# 08_Programming_Reset.net
KiCad netlist of a schematic drawn in Altium Designer
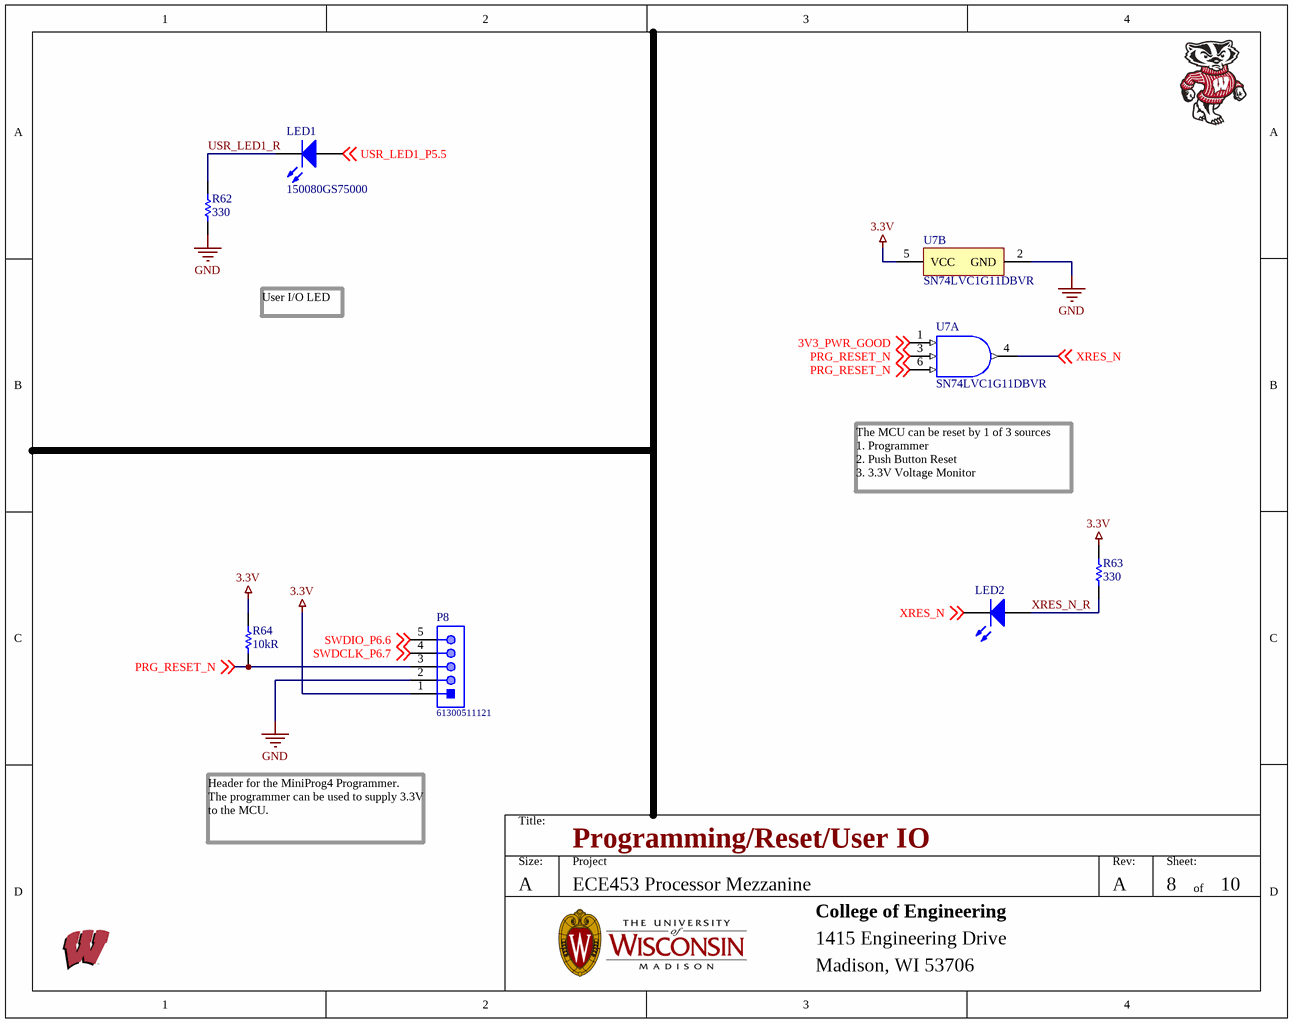
[diagram p0: 08_Programming_Reset.SchDoc]

(export (version "E")
  (design (tool "Eeschema 10.0.6"))
  (components
    (comp (ref "LED1")
      (value "150080GS75000")
      (footprint "0805_A")
      (description "SMD mono-color Chip LED, WL-SMCW, Green")
      (fields (field (name "MANUFACTURER") "Wuerth Elektronik"))
      (libsource (lib "Altium Content Vault") (part "WE-LED_K1A2-2"))
    )
    (comp (ref "LED2")
      (value "150080RS75000")
      (footprint "0805_A")
      (description "SMD mono-color Chip LED, WL-SMCW, Red")
      (fields (field (name "MANUFACTURER") "Wuerth Elektronik"))
      (libsource (lib "Altium Content Vault") (part "WE-LED_K1A2-2"))
    )
    (comp (ref "P8")
      (value "61300511121")
      (footprint "61300511121")
      (description "THT Vertical Pin Header WR-PHD, Pitch 2.54 mm, Single Row, 5 pins")
      (fields (field (name "MANUFACTURER") "Wurth Elektronik") (field (name "PUBLISHER") "WurthElektronik"))
      (libsource (lib "Altium Content Vault") (part "WE-CN-1P-M-R5"))
    )
    (comp (ref "R62")
      (value "RC0805FR-07330RL")
      (footprint "RESC2013X60X35LL10T20")
      (description "Chip Resistor, 330 Ohm, +/- 1%, 125 mW, -55 to 155 degC, 0805 (2012 Metric), RoHS, Tape and Reel")
      (fields
        (field (name "MANUFACTURER") "Yageo")
        (field (name "TOLERANCE") "1%")
        (field (name "RESISTANCE") "330")
      )
      (libsource (lib "Altium Content Vault") (part "RES-2"))
    )
    (comp (ref "R63")
      (value "RC0805FR-07330RL")
      (footprint "RESC2013X60X35LL10T20")
      (description "Chip Resistor, 330 Ohm, +/- 1%, 125 mW, -55 to 155 degC, 0805 (2012 Metric), RoHS, Tape and Reel")
      (fields
        (field (name "MANUFACTURER") "Yageo")
        (field (name "TOLERANCE") "1%")
        (field (name "RESISTANCE") "330")
      )
      (libsource (lib "Altium Content Vault") (part "RES-2"))
    )
    (comp (ref "R64")
      (value "RC0805FR-0710KL")
      (footprint "RESC2013X60X35NL10T20")
      (description "Chip Resistor, 10 KOhm, +/- 1%, 0.125 W, -55 to 155 degC, 0805 (2012 Metric), RoHS, Tape and Reel")
      (fields
        (field (name "MANUFACTURER") "Yageo")
        (field (name "RESISTANCE") "10kR")
        (field (name "TOLERANCE") "1%")
      )
      (libsource (lib "Altium Content Vault") (part "RES-2"))
    )
    (comp (ref "U7")
      (value "SN74LVC1G11DBVR")
      (footprint "DBV0006A_N")
      (description "Single 3-Input Positive-AND Gate, DBV0006A, LARGE T&R")
      (fields
        (field (name "MANUFACTURER") "Texas Instruments")
        (field (name "GENERIC PART NUMBER") "SN74LVC1G11")
      )
      (libsource (lib "Altium Content Vault") (part "TI-AND-1-3IN-6"))
    )
  )
  (nets
    (net (code "1") (name "/USR_LED1_R") (class "Default")
      (node (ref "LED1") (pin "1") (pinfunction "K_1") (pintype "passive"))
      (node (ref "R62") (pin "2") (pinfunction "2_2") (pintype "passive"))
    )
    (net (code "2") (name "/XRES_N_R") (class "Default")
      (node (ref "LED2") (pin "2") (pinfunction "A_2") (pintype "passive"))
      (node (ref "R63") (pin "1") (pinfunction "1_1") (pintype "passive"))
    )
    (net (code "3") (name "3.3V") (class "Default")
      (node (ref "P8") (pin "1") (pinfunction "1_1") (pintype "passive"))
      (node (ref "R63") (pin "2") (pinfunction "2_2") (pintype "passive"))
      (node (ref "R64") (pin "2") (pinfunction "2_2") (pintype "passive"))
      (node (ref "U7") (pin "5") (pinfunction "VCC_5") (pintype "power_in"))
    )
    (net (code "4") (name "3V3_PWR_GOOD") (class "Default")
      (node (ref "U7") (pin "1") (pinfunction "A_1") (pintype "input"))
    )
    (net (code "5") (name "GND") (class "Default")
      (node (ref "P8") (pin "2") (pinfunction "2_2") (pintype "passive"))
      (node (ref "R62") (pin "1") (pinfunction "1_1") (pintype "passive"))
      (node (ref "U7") (pin "2") (pinfunction "GND_2") (pintype "power_in"))
    )
    (net (code "6") (name "PRG_RESET_N") (class "Default")
      (node (ref "P8") (pin "3") (pinfunction "3_3") (pintype "passive"))
      (node (ref "R64") (pin "1") (pinfunction "1_1") (pintype "passive"))
      (node (ref "U7") (pin "3") (pinfunction "B_3") (pintype "input"))
      (node (ref "U7") (pin "6") (pinfunction "C_6") (pintype "input"))
    )
    (net (code "7") (name "SWDCLK_P6.7") (class "Default")
      (node (ref "P8") (pin "4") (pinfunction "4_4") (pintype "passive"))
    )
    (net (code "8") (name "SWDIO_P6.6") (class "Default")
      (node (ref "P8") (pin "5") (pinfunction "5_5") (pintype "passive"))
    )
    (net (code "9") (name "USR_LED1_P5.5") (class "Default")
      (node (ref "LED1") (pin "2") (pinfunction "A_2") (pintype "passive"))
    )
    (net (code "10") (name "XRES_N") (class "Default")
      (node (ref "LED2") (pin "1") (pinfunction "K_1") (pintype "passive"))
      (node (ref "U7") (pin "4") (pinfunction "Y_4") (pintype "output"))
    )
  )
)
